# PWR_P2V5A.net
KiCad netlist of a schematic drawn in Altium Designer
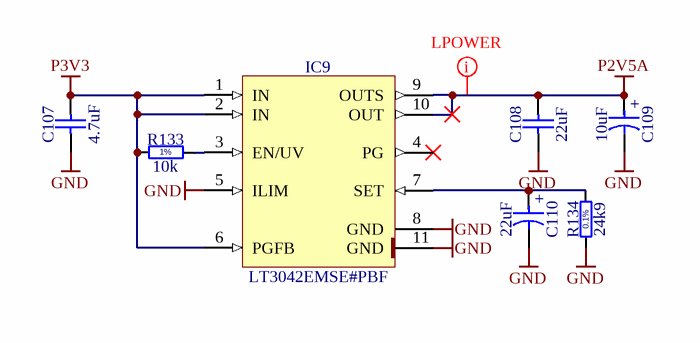
[diagram p0: PWR_P2V5A.SchDoc]

(export (version "E")
  (design (tool "Eeschema 10.0.6"))
  (components
    (comp (ref "C107")
      (value "4.7uF")
      (footprint "CAPC1709X95N")
      (description "Non-polarised capacitor")
      (fields
        (field (name "PART NUMBER") "CC0603_4.7UF_16V_10%_X5R")
        (field (name "VOLTAGE") "16V")
        (field (name "AUTHOR") "CERN DEM JLC")
      )
      (libsource (lib "Capacitors") (part "Capacitor - non polarized"))
    )
    (comp (ref "C108")
      (value "22uF")
      (footprint "CAPC2012X135N")
      (description "Non-polarised capacitor")
      (fields
        (field (name "PART NUMBER") "CC0805_22UF_16V_10%_X5R")
        (field (name "VOLTAGE") "16V")
        (field (name "AUTHOR") "CERN DEM JLC")
      )
      (libsource (lib "Capacitors") (part "Capacitor - non polarized"))
    )
    (comp (ref "C109")
      (value "10uF")
      (footprint "CAPMP3216X180N")
      (description "Polarised capacitor")
      (fields
        (field (name "PART NUMBER") "CTE3216-18_10UF_16V_20%_AVX_TCJ")
        (field (name "VOLTAGE") "16V")
        (field (name "AUTHOR") "CERN DEM JLC")
      )
      (libsource (lib "Capacitors") (part "Capacitor - polarized"))
    )
    (comp (ref "C110")
      (value "22uF")
      (footprint "CAPMP3216X180N")
      (description "Polarised capacitor")
      (fields
        (field (name "PART NUMBER") "CTE3216-18_22UF_10V_10%")
        (field (name "VOLTAGE") "10V")
        (field (name "AUTHOR") "CERN DEM JLC")
      )
      (libsource (lib "Capacitors") (part "Capacitor - polarized"))
    )
    (comp (ref "IC9")
      (value "LT3042EMSE#PBF")
      (footprint "SOP50P490X110-11N-R168X198")
      (description "20V, 200mA, Ultralow Noise, Ultrahigh PSRR RF Linear Regulator")
      (fields (field (name "MANUFACTURER") "LINEAR TECHNOLOGY") (field (name "AUTHOR") "CERN DEM MR"))
      (libsource (lib "ICs And Semiconductors") (part "LT3042"))
    )
    (comp (ref "R133")
      (value "10k")
      (footprint "RESC1005X40N")
      (description "Resistor - 1%")
      (fields
        (field (name "PART NUMBER") "R0402_10K_1%_0.0625W_100PPM")
        (field (name "POWER") "0.0625W")
        (field (name "AUTHOR") "CERN DEM JLC")
      )
      (libsource (lib "Resistors") (part "Resistor - 1%"))
    )
    (comp (ref "R134")
      (value "24k9")
      (footprint "RESC1608X55N")
      (description "Resistor - 0.1%")
      (fields
        (field (name "PART NUMBER") "R0603_24K9_0.1%_0.063W_10PPM")
        (field (name "POWER") "0.063W")
        (field (name "AUTHOR") "CERN DEM JLC")
      )
      (libsource (lib "Resistors") (part "Resistor - 0.1%"))
    )
  )
  (nets
    (net (code "1") (name "GND") (class "Default")
      (node (ref "C107") (pin "1") (pinfunction "1_1") (pintype "passive"))
      (node (ref "C108") (pin "1") (pinfunction "1_1") (pintype "passive"))
      (node (ref "C109") (pin "2") (pinfunction "2_2") (pintype "passive"))
      (node (ref "C110") (pin "2") (pinfunction "2_2") (pintype "passive"))
      (node (ref "IC9") (pin "11") (pinfunction "GND_11") (pintype "power_in"))
      (node (ref "IC9") (pin "5") (pinfunction "ILIM_5") (pintype "input"))
      (node (ref "IC9") (pin "8") (pinfunction "GND_8") (pintype "power_in"))
      (node (ref "R134") (pin "1") (pinfunction "1_1") (pintype "passive"))
    )
    (net (code "2") (name "Net-(IC9-EN{slash}UV)") (class "Default")
      (node (ref "IC9") (pin "3") (pinfunction "EN/UV_3") (pintype "input"))
      (node (ref "R133") (pin "2") (pinfunction "2_2") (pintype "passive"))
    )
    (net (code "3") (name "Net-(IC9-SET)") (class "Default")
      (node (ref "C110") (pin "1") (pinfunction "1_1") (pintype "passive"))
      (node (ref "IC9") (pin "7") (pinfunction "SET_7") (pintype "input"))
      (node (ref "R134") (pin "2") (pinfunction "2_2") (pintype "passive"))
    )
    (net (code "4") (name "P2V5A") (class "Default")
      (node (ref "C108") (pin "2") (pinfunction "2_2") (pintype "passive"))
      (node (ref "C109") (pin "1") (pinfunction "1_1") (pintype "passive"))
      (node (ref "IC9") (pin "10") (pinfunction "OUT_10") (pintype "output"))
      (node (ref "IC9") (pin "9") (pinfunction "OUTS_9") (pintype "output"))
    )
    (net (code "5") (name "P3V3") (class "Default")
      (node (ref "C107") (pin "2") (pinfunction "2_2") (pintype "passive"))
      (node (ref "IC9") (pin "1") (pinfunction "IN_1") (pintype "input"))
      (node (ref "IC9") (pin "2") (pinfunction "IN_2") (pintype "input"))
      (node (ref "IC9") (pin "6") (pinfunction "PGFB_6") (pintype "input"))
      (node (ref "R133") (pin "1") (pinfunction "1_1") (pintype "passive"))
    )
    (net (code "6") (name "unconnected-(IC9-PG-Pad4)") (class "Default")
      (node (ref "IC9") (pin "4") (pinfunction "PG_4") (pintype "output+no_connect"))
    )
  )
)
